# LP2985_3v3.net
KiCad netlist of a schematic drawn in EAGLE
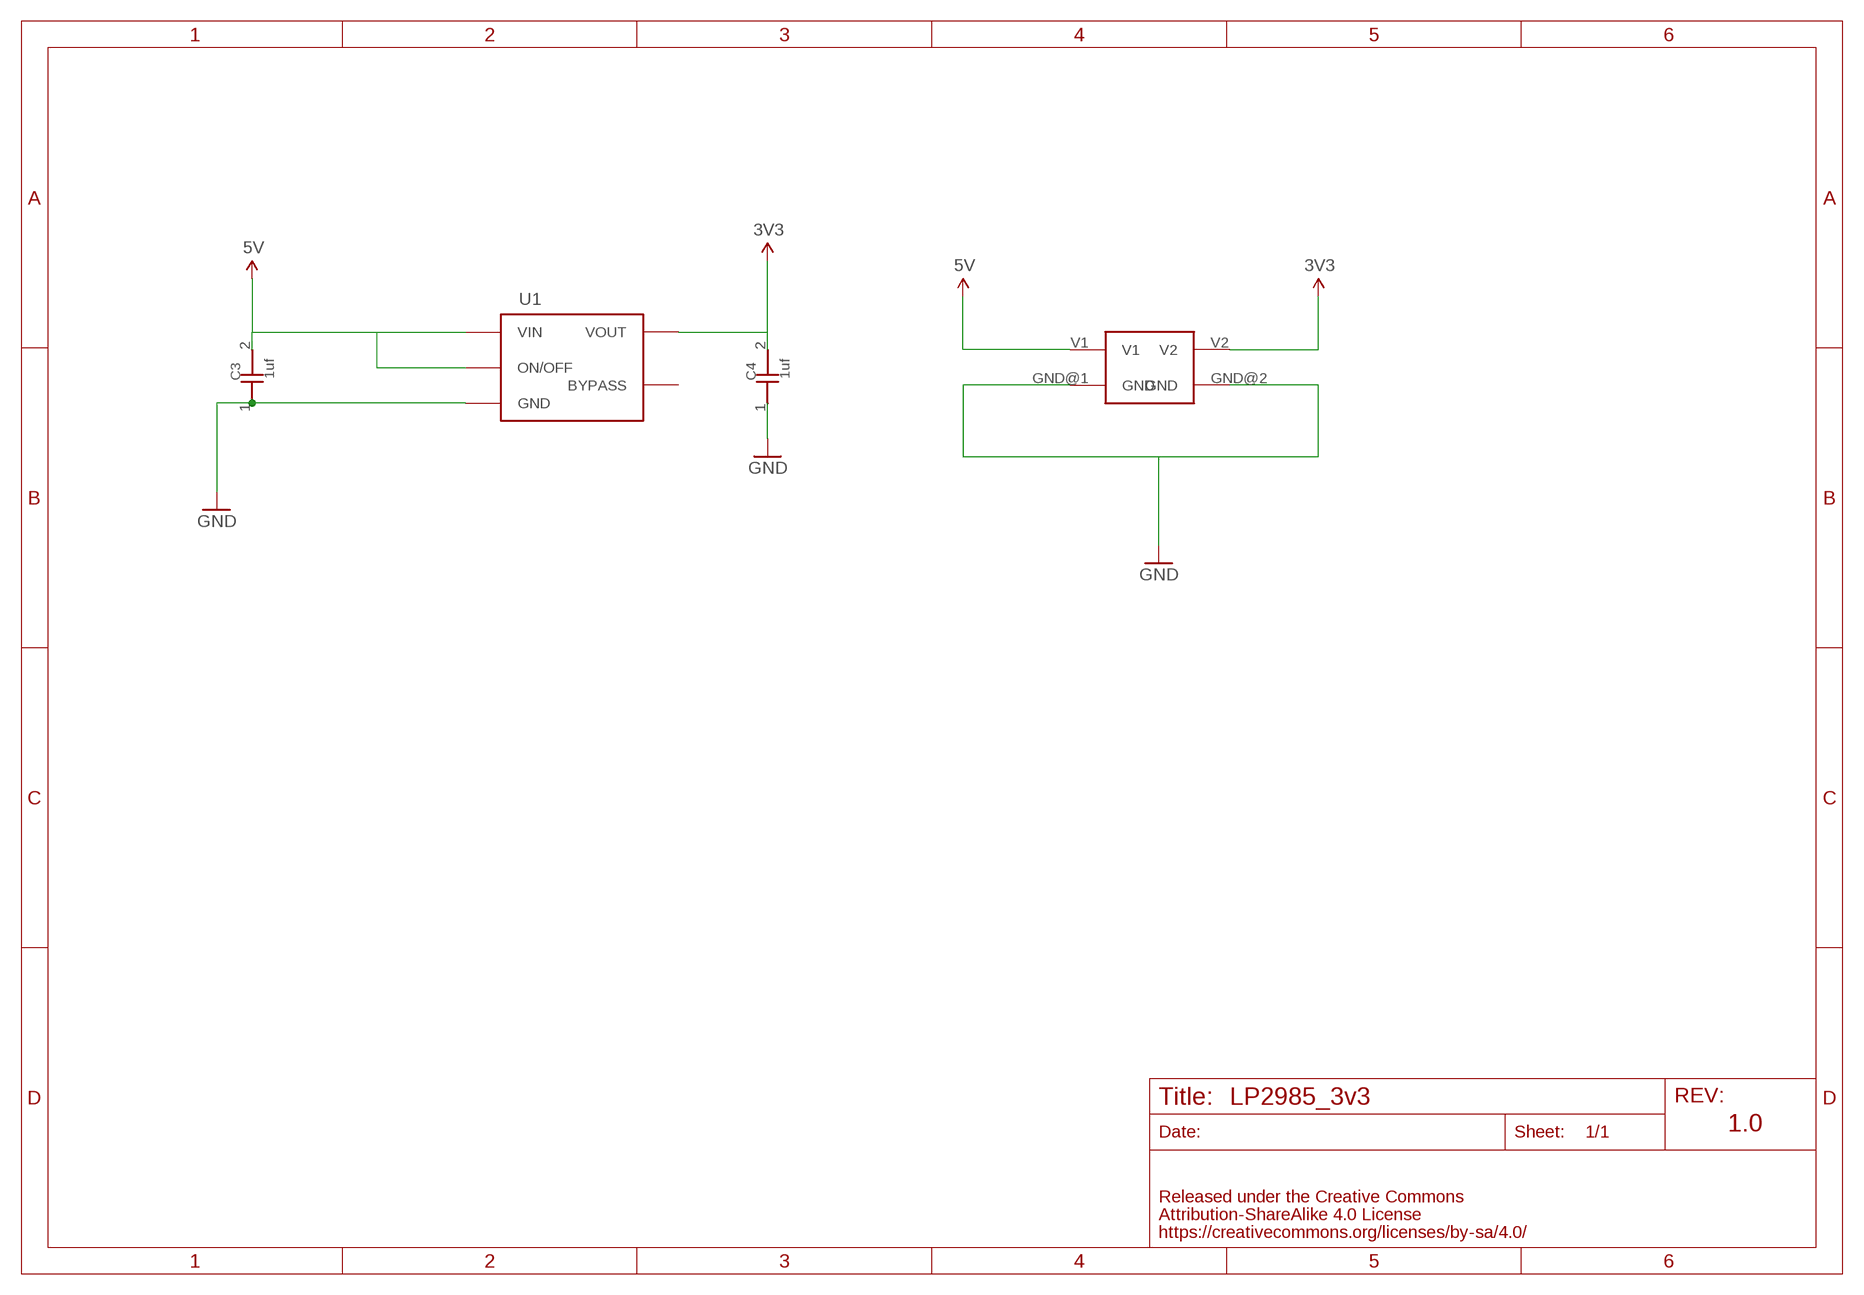
[diagram p0: schematic, sheet 1]

(export (version "E")
  (design (tool "Eeschema 10.0.6"))
  (components
    (comp (ref "C3")
      (value "1uf")
      (footprint "eagle-import:0603")
      (libsource (lib "eagle-import") (part "CAPACITOR0603"))
    )
    (comp (ref "C4")
      (value "1uf")
      (footprint "eagle-import:0603")
      (libsource (lib "eagle-import") (part "CAPACITOR0603"))
    )
    (comp (ref "U$2")
      (value "4PIN-REGULATOR")
      (footprint "eagle-import:4PIN-REGULATOR")
      (libsource (lib "eagle-import") (part "4PIN-REGULATOR"))
    )
    (comp (ref "U1")
      (value "LP2985-33DBVR")
      (footprint "eagle-import:SOT_23_5")
      (libsource (lib "eagle-import") (part "LP2985-33DBVR"))
    )
  )
  (nets
    (net (code "1") (name "3V3") (class "Default")
      (node (ref "C4") (pin "2") (pinfunction "2_2") (pintype "passive"))
      (node (ref "U$2") (pin "V2") (pinfunction "V2_V2") (pintype "bidirectional"))
      (node (ref "U1") (pin "5") (pinfunction "VOUT_5") (pintype "output"))
    )
    (net (code "2") (name "5V") (class "Default")
      (node (ref "C3") (pin "2") (pinfunction "2_2") (pintype "passive"))
      (node (ref "U$2") (pin "V1") (pinfunction "V1_V1") (pintype "bidirectional"))
      (node (ref "U1") (pin "1") (pinfunction "VIN_1") (pintype "input"))
      (node (ref "U1") (pin "3") (pinfunction "ON/OFF_3") (pintype "input"))
    )
    (net (code "3") (name "GND") (class "Default")
      (node (ref "C3") (pin "1") (pinfunction "1_1") (pintype "passive"))
      (node (ref "C4") (pin "1") (pinfunction "1_1") (pintype "passive"))
      (node (ref "U$2") (pin "GND@1") (pinfunction "GND_GND@1") (pintype "bidirectional"))
      (node (ref "U$2") (pin "GND@2") (pinfunction "GND_GND@2") (pintype "bidirectional"))
      (node (ref "U1") (pin "2") (pinfunction "GND_2") (pintype "power_in"))
    )
    (net (code "4") (name "unconnected-(U1-BYPASS-Pad4)") (class "Default")
      (node (ref "U1") (pin "4") (pinfunction "BYPASS_4") (pintype "bidirectional"))
    )
  )
)
